# WDT_Supervisory.net
KiCad netlist of a schematic drawn in Altium Designer
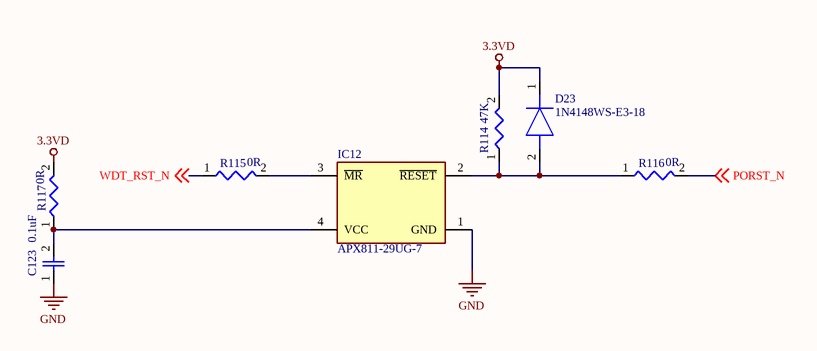
[diagram p0: WDT_Supervisory.SchDoc]

(export (version "E")
  (design (tool "Eeschema 10.0.6"))
  (components
    (comp (ref "C123")
      (value "0.1uF")
      (footprint "0603-C")
      (libsource (lib "OOLITEV8_0_2-DEV-V1_1_17") (part "CAP"))
    )
    (comp (ref "D23")
      (value "1N4148WS-E3-18")
      (footprint "SamacSys:SOD2713X115N")
      (description "Diode")
      (fields (field (name "MOUSER PART NUMBER") "78-1N4148WS-E3-18"))
      (libsource (lib "*") (part "1N4148WS-E3-18"))
    )
    (comp (ref "IC12")
      (value "APX811-29UG-7")
      (footprint "SOT143")
      (description "Supervisory Circuits 4-Pin MPU Supervisor")
      (libsource (lib "IIOT_GATEWAY_MT7621") (part "APX811-29UG-7"))
    )
    (comp (ref "R114")
      (value "47K")
      (footprint "0402-R")
      (libsource (lib "OOLITEV8_0_2-DEV-V1_1_17") (part "Res"))
    )
    (comp (ref "R115")
      (value "0R")
      (footprint "0402-R")
      (libsource (lib "OOLITEV8_0_2-DEV-V1_1_17") (part "Res"))
    )
    (comp (ref "R116")
      (value "0R")
      (footprint "0402-R")
      (libsource (lib "OOLITEV8_0_2-DEV-V1_1_17") (part "Res"))
    )
    (comp (ref "R117")
      (value "0R")
      (footprint "0402-R")
      (libsource (lib "OOLITEV8_0_2-DEV-V1_1_17") (part "Res"))
    )
  )
  (nets
    (net (code "1") (name "3.3VD") (class "Default")
      (node (ref "D23") (pin "1") (pinfunction "K_1") (pintype "passive"))
      (node (ref "R114") (pin "2") (pinfunction "2_2") (pintype "passive"))
      (node (ref "R117") (pin "2") (pinfunction "2_2") (pintype "passive"))
    )
    (net (code "2") (name "GND") (class "Default")
      (node (ref "C123") (pin "1") (pinfunction "1_1") (pintype "passive"))
      (node (ref "IC12") (pin "1") (pinfunction "GND_1") (pintype "passive"))
    )
    (net (code "3") (name "Net-(D23-A)") (class "Default")
      (node (ref "D23") (pin "2") (pinfunction "A_2") (pintype "passive"))
      (node (ref "IC12") (pin "2") (pinfunction "~{RESET}_2") (pintype "passive"))
      (node (ref "R114") (pin "1") (pinfunction "1_1") (pintype "passive"))
      (node (ref "R116") (pin "1") (pinfunction "1_1") (pintype "passive"))
    )
    (net (code "4") (name "Net-(IC12-VCC)") (class "Default")
      (node (ref "C123") (pin "2") (pinfunction "2_2") (pintype "passive"))
      (node (ref "IC12") (pin "4") (pinfunction "VCC_4") (pintype "passive"))
      (node (ref "R117") (pin "1") (pinfunction "1_1") (pintype "passive"))
    )
    (net (code "5") (name "Net-(IC12-~{MR})") (class "Default")
      (node (ref "IC12") (pin "3") (pinfunction "~{MR}_3") (pintype "passive"))
      (node (ref "R115") (pin "2") (pinfunction "2_2") (pintype "passive"))
    )
    (net (code "6") (name "PORST_N") (class "Default")
      (node (ref "R116") (pin "2") (pinfunction "2_2") (pintype "passive"))
    )
    (net (code "7") (name "WDT_RST_N") (class "Default")
      (node (ref "R115") (pin "1") (pinfunction "1_1") (pintype "passive"))
    )
  )
)
